# smoothieboard_daugterboard_template.net
KiCad netlist of a schematic drawn in EAGLE
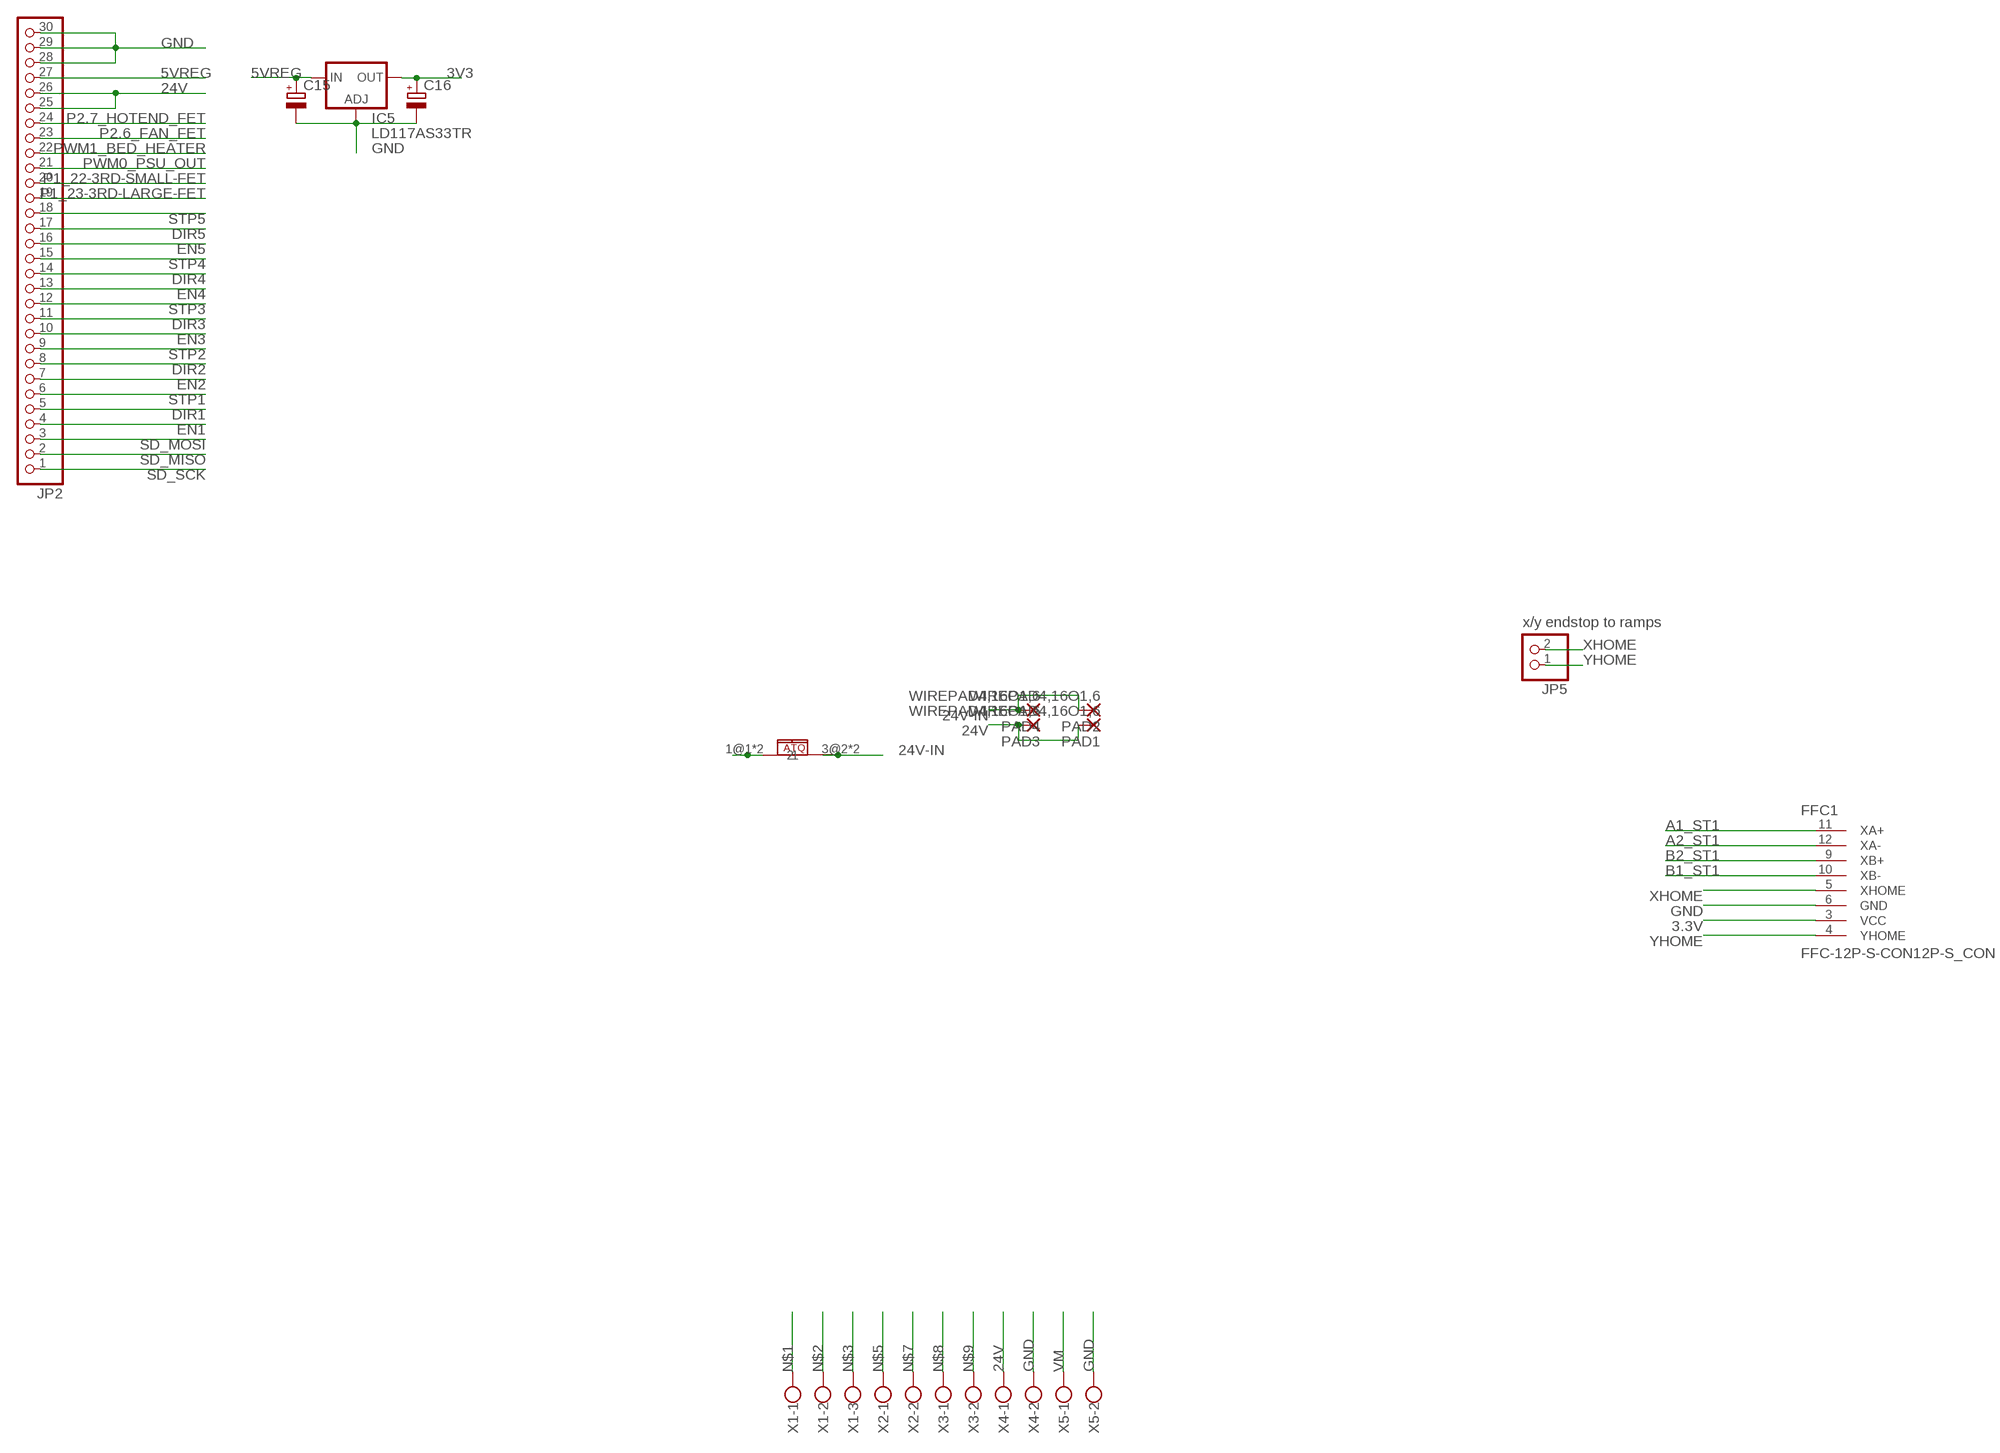
[diagram p0: schematic, sheet 1]

(export (version "E")
  (design (tool "Eeschema 10.0.6"))
  (components
    (comp (ref "C15")
      (value "CPOL-EUE2.5-7")
      (footprint "eagle-import:E2,5-7")
      (libsource (lib "eagle-import") (part "CPOL-EUE2.5-7"))
    )
    (comp (ref "C16")
      (value "CPOL-EUE2.5-6")
      (footprint "eagle-import:E2,5-6")
      (libsource (lib "eagle-import") (part "CPOL-EUE2.5-6"))
    )
    (comp (ref "FFC1")
      (value "FFC-12P-S-CON12P-S_CON")
      (footprint "eagle-import:FFC")
      (libsource (lib "eagle-import") (part "FFC-12P-S-CON12P-S_CON"))
    )
    (comp (ref "IC5")
      (value "LD117AS33TR")
      (footprint "eagle-import:SOT223")
      (libsource (lib "eagle-import") (part "LD117A?S33TR"))
    )
    (comp (ref "JP2")
      (value "PINHD-1X30")
      (footprint "eagle-import:1X30")
      (libsource (lib "eagle-import") (part "PINHD-1X30"))
    )
    (comp (ref "JP5")
      (value "PINHD-1X2")
      (footprint "eagle-import:1X02")
      (libsource (lib "eagle-import") (part "PINHD-1X2"))
    )
    (comp (ref "PAD1")
      (value "WIREPAD4,16O1,6")
      (footprint "eagle-import:4,16O1,6")
      (libsource (lib "eagle-import") (part "WIREPAD4,16O1,6"))
    )
    (comp (ref "PAD2")
      (value "WIREPAD4,16O1,6")
      (footprint "eagle-import:4,16O1,6")
      (libsource (lib "eagle-import") (part "WIREPAD4,16O1,6"))
    )
    (comp (ref "PAD3")
      (value "WIREPAD4,16O1,6")
      (footprint "eagle-import:4,16O1,6")
      (libsource (lib "eagle-import") (part "WIREPAD4,16O1,6"))
    )
    (comp (ref "PAD4")
      (value "WIREPAD4,16O1,6")
      (footprint "eagle-import:4,16O1,6")
      (libsource (lib "eagle-import") (part "WIREPAD4,16O1,6"))
    )
    (comp (ref "U$7")
      (value "CQ-121")
      (footprint "eagle-import:CQ121")
      (libsource (lib "eagle-import") (part "CQ-121"))
    )
    (comp (ref "X1")
      (value "W237-103")
      (footprint "eagle-import:W237-103")
      (fields (field (name "MPN") "237-103"))
      (libsource (lib "eagle-import") (part "W237-103"))
    )
    (comp (ref "X2")
      (value "W237-102")
      (footprint "eagle-import:W237-102")
      (fields (field (name "MPN") "237-102"))
      (libsource (lib "eagle-import") (part "W237-102"))
    )
    (comp (ref "X3")
      (value "W237-102")
      (footprint "eagle-import:W237-102")
      (fields (field (name "MPN") "237-102"))
      (libsource (lib "eagle-import") (part "W237-102"))
    )
    (comp (ref "X4")
      (value "W237-102")
      (footprint "eagle-import:W237-102")
      (fields (field (name "MPN") "237-102"))
      (libsource (lib "eagle-import") (part "W237-102"))
    )
    (comp (ref "X5")
      (value "W237-102")
      (footprint "eagle-import:W237-102")
      (fields (field (name "MPN") "237-102"))
      (libsource (lib "eagle-import") (part "W237-102"))
    )
  )
  (nets
    (net (code "1") (name "/3.3V") (class "Default")
      (node (ref "FFC1") (pin "3") (pinfunction "VCC_3") (pintype "power_in"))
    )
    (net (code "2") (name "/3V3") (class "Default")
      (node (ref "C16") (pin "+") (pinfunction "+_+") (pintype "passive"))
      (node (ref "IC5") (pin "4") (pinfunction "OUT_4") (pintype "passive"))
    )
    (net (code "3") (name "/5VREG") (class "Default")
      (node (ref "C15") (pin "+") (pinfunction "+_+") (pintype "passive"))
      (node (ref "IC5") (pin "3") (pinfunction "IN_3") (pintype "input"))
      (node (ref "JP2") (pin "27") (pinfunction "27_27") (pintype "passive"))
    )
    (net (code "4") (name "/24V") (class "Default")
      (node (ref "JP2") (pin "25") (pinfunction "25_25") (pintype "passive"))
      (node (ref "JP2") (pin "26") (pinfunction "26_26") (pintype "passive"))
      (node (ref "PAD1") (pin "1") (pinfunction "P_1") (pintype "passive"))
      (node (ref "PAD3") (pin "1") (pinfunction "P_1") (pintype "passive"))
      (node (ref "X4") (pin "1") (pinfunction "KL_1") (pintype "passive"))
    )
    (net (code "5") (name "/24V-IN") (class "Default")
      (node (ref "PAD2") (pin "1") (pinfunction "P_1") (pintype "passive"))
      (node (ref "PAD4") (pin "1") (pinfunction "P_1") (pintype "passive"))
      (node (ref "U$7") (pin "3@2") (pinfunction "2_3@2") (pintype "bidirectional"))
      (node (ref "U$7") (pin "4@2") (pinfunction "2_4@2") (pintype "bidirectional"))
    )
    (net (code "6") (name "/A1_ST1") (class "Default")
      (node (ref "FFC1") (pin "11") (pinfunction "XA+_11") (pintype "bidirectional"))
    )
    (net (code "7") (name "/A2_ST1") (class "Default")
      (node (ref "FFC1") (pin "12") (pinfunction "XA-_12") (pintype "bidirectional"))
    )
    (net (code "8") (name "/B1_ST1") (class "Default")
      (node (ref "FFC1") (pin "10") (pinfunction "XB-_10") (pintype "bidirectional"))
    )
    (net (code "9") (name "/B2_ST1") (class "Default")
      (node (ref "FFC1") (pin "9") (pinfunction "XB+_9") (pintype "bidirectional"))
    )
    (net (code "10") (name "/DIR1") (class "Default")
      (node (ref "JP2") (pin "5") (pinfunction "5_5") (pintype "passive"))
    )
    (net (code "11") (name "/DIR2") (class "Default")
      (node (ref "JP2") (pin "8") (pinfunction "8_8") (pintype "passive"))
    )
    (net (code "12") (name "/DIR3") (class "Default")
      (node (ref "JP2") (pin "11") (pinfunction "11_11") (pintype "passive"))
    )
    (net (code "13") (name "/DIR4") (class "Default")
      (node (ref "JP2") (pin "14") (pinfunction "14_14") (pintype "passive"))
    )
    (net (code "14") (name "/DIR5") (class "Default")
      (node (ref "JP2") (pin "17") (pinfunction "17_17") (pintype "passive"))
    )
    (net (code "15") (name "/EN1") (class "Default")
      (node (ref "JP2") (pin "4") (pinfunction "4_4") (pintype "passive"))
    )
    (net (code "16") (name "/EN2") (class "Default")
      (node (ref "JP2") (pin "7") (pinfunction "7_7") (pintype "passive"))
    )
    (net (code "17") (name "/EN3") (class "Default")
      (node (ref "JP2") (pin "10") (pinfunction "10_10") (pintype "passive"))
    )
    (net (code "18") (name "/EN4") (class "Default")
      (node (ref "JP2") (pin "13") (pinfunction "13_13") (pintype "passive"))
    )
    (net (code "19") (name "/EN5") (class "Default")
      (node (ref "JP2") (pin "16") (pinfunction "16_16") (pintype "passive"))
    )
    (net (code "20") (name "/GND") (class "Default")
      (node (ref "C15") (pin "-") (pinfunction "-_-") (pintype "passive"))
      (node (ref "C16") (pin "-") (pinfunction "-_-") (pintype "passive"))
      (node (ref "FFC1") (pin "6") (pinfunction "GND_6") (pintype "power_in"))
      (node (ref "IC5") (pin "1") (pinfunction "ADJ_1") (pintype "input"))
      (node (ref "JP2") (pin "28") (pinfunction "28_28") (pintype "passive"))
      (node (ref "JP2") (pin "29") (pinfunction "29_29") (pintype "passive"))
      (node (ref "JP2") (pin "30") (pinfunction "30_30") (pintype "passive"))
      (node (ref "X4") (pin "2") (pinfunction "KL_2") (pintype "passive"))
      (node (ref "X5") (pin "2") (pinfunction "KL_2") (pintype "passive"))
    )
    (net (code "21") (name "/N$1") (class "Default")
      (node (ref "X1") (pin "1") (pinfunction "KL_1") (pintype "passive"))
    )
    (net (code "22") (name "/N$2") (class "Default")
      (node (ref "X1") (pin "2") (pinfunction "KL_2") (pintype "passive"))
    )
    (net (code "23") (name "/N$3") (class "Default")
      (node (ref "X1") (pin "3") (pinfunction "KL_3") (pintype "passive"))
    )
    (net (code "24") (name "/N$5") (class "Default")
      (node (ref "X2") (pin "1") (pinfunction "KL_1") (pintype "passive"))
    )
    (net (code "25") (name "/N$7") (class "Default")
      (node (ref "X2") (pin "2") (pinfunction "KL_2") (pintype "passive"))
    )
    (net (code "26") (name "/N$8") (class "Default")
      (node (ref "X3") (pin "1") (pinfunction "KL_1") (pintype "passive"))
    )
    (net (code "27") (name "/N$9") (class "Default")
      (node (ref "X3") (pin "2") (pinfunction "KL_2") (pintype "passive"))
    )
    (net (code "28") (name "/P1_22-3RD-SMALL-FET") (class "Default")
      (node (ref "JP2") (pin "20") (pinfunction "20_20") (pintype "passive"))
    )
    (net (code "29") (name "/P1_23-3RD-LARGE-FET") (class "Default")
      (node (ref "JP2") (pin "19") (pinfunction "19_19") (pintype "passive"))
    )
    (net (code "30") (name "/P2.6_FAN_FET") (class "Default")
      (node (ref "JP2") (pin "23") (pinfunction "23_23") (pintype "passive"))
    )
    (net (code "31") (name "/P2.7_HOTEND_FET") (class "Default")
      (node (ref "JP2") (pin "24") (pinfunction "24_24") (pintype "passive"))
    )
    (net (code "32") (name "/PWM0_PSU_OUT") (class "Default")
      (node (ref "JP2") (pin "21") (pinfunction "21_21") (pintype "passive"))
    )
    (net (code "33") (name "/PWM1_BED_HEATER") (class "Default")
      (node (ref "JP2") (pin "22") (pinfunction "22_22") (pintype "passive"))
    )
    (net (code "34") (name "/SD_MISO") (class "Default")
      (node (ref "JP2") (pin "2") (pinfunction "2_2") (pintype "passive"))
    )
    (net (code "35") (name "/SD_MOSI") (class "Default")
      (node (ref "JP2") (pin "3") (pinfunction "3_3") (pintype "passive"))
    )
    (net (code "36") (name "/SD_SCK") (class "Default")
      (node (ref "JP2") (pin "1") (pinfunction "1_1") (pintype "passive"))
    )
    (net (code "37") (name "/STP1") (class "Default")
      (node (ref "JP2") (pin "6") (pinfunction "6_6") (pintype "passive"))
    )
    (net (code "38") (name "/STP2") (class "Default")
      (node (ref "JP2") (pin "9") (pinfunction "9_9") (pintype "passive"))
    )
    (net (code "39") (name "/STP3") (class "Default")
      (node (ref "JP2") (pin "12") (pinfunction "12_12") (pintype "passive"))
    )
    (net (code "40") (name "/STP4") (class "Default")
      (node (ref "JP2") (pin "15") (pinfunction "15_15") (pintype "passive"))
    )
    (net (code "41") (name "/STP5") (class "Default")
      (node (ref "JP2") (pin "18") (pinfunction "18_18") (pintype "passive"))
    )
    (net (code "42") (name "/VM") (class "Default")
      (node (ref "U$7") (pin "1@1") (pinfunction "1_1@1") (pintype "bidirectional"))
      (node (ref "U$7") (pin "2@1") (pinfunction "1_2@1") (pintype "bidirectional"))
      (node (ref "X5") (pin "1") (pinfunction "KL_1") (pintype "passive"))
    )
    (net (code "43") (name "/XHOME") (class "Default")
      (node (ref "FFC1") (pin "5") (pinfunction "XHOME_5") (pintype "bidirectional"))
      (node (ref "JP5") (pin "2") (pinfunction "2_2") (pintype "passive"))
    )
    (net (code "44") (name "/YHOME") (class "Default")
      (node (ref "FFC1") (pin "4") (pinfunction "YHOME_4") (pintype "bidirectional"))
      (node (ref "JP5") (pin "1") (pinfunction "1_1") (pintype "passive"))
    )
  )
)
